# schematic.net
KiCad netlist of a schematic drawn in EasyEDA
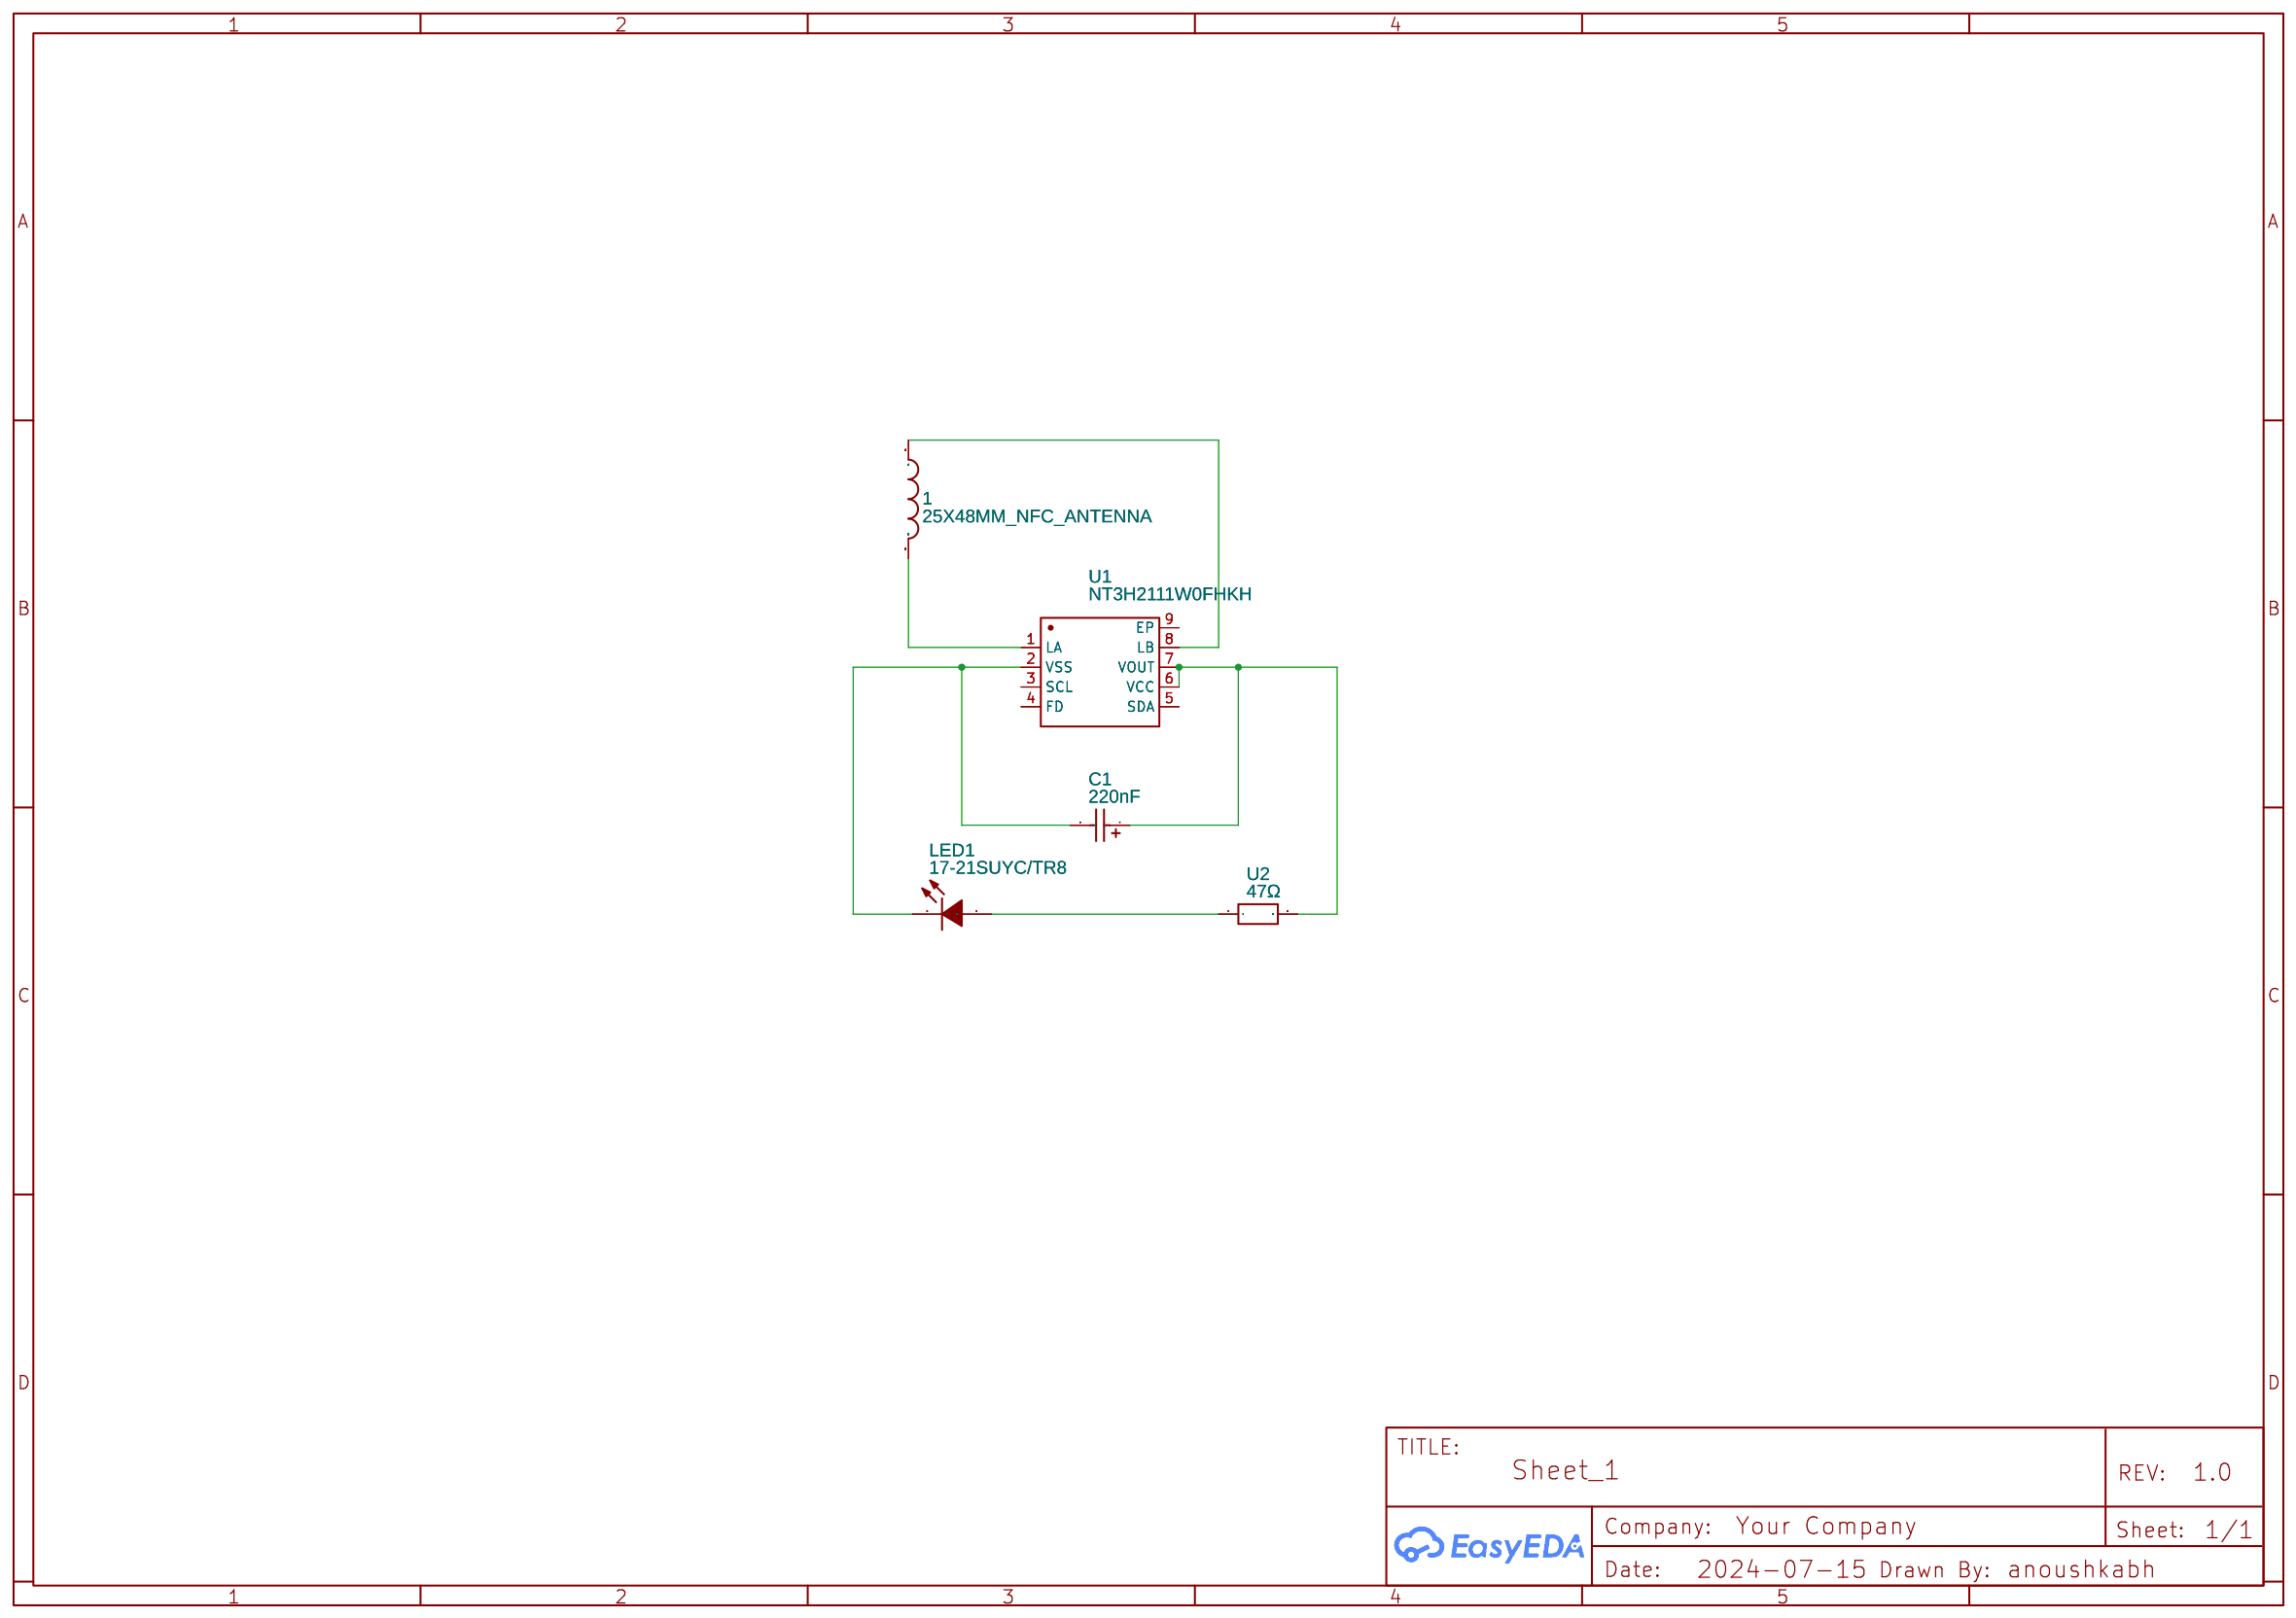
[diagram p0: schematic sheet]

(export (version "E")
  (design (tool "Eeschema 10.0.6"))
  (components
    (comp (ref "1") (value "25X48MM_NFC_ANTENNA") (libsource (lib "") (part "25X48MM_NFC_ANTENNA")))
    (comp (ref "C1")
      (value "220nF")
      (fields (field (name "Manufacturer Part") "TAJA224K035RNJ") (field (name "Manufacturer") "Kyocera AVX"))
      (libsource (lib "") (part "TAJA224K035RNJ"))
    )
    (comp (ref "LED1")
      (value "17-21SUYC/TR8")
      (fields (field (name "Manufacturer Part") "KT-0805黄灯") (field (name "Manufacturer") "KENTO"))
      (libsource (lib "") (part "17-21SUYC/TR8"))
    )
    (comp (ref "U1")
      (value "NT3H2111W0FHKH")
      (fields (field (name "Manufacturer") "NXP(恩智浦)"))
      (libsource (lib "") (part "NT3H2111W0FHKH"))
    )
    (comp (ref "U2")
      (value "47Ω")
      (fields (field (name "Manufacturer Part") "KNP1WS-47Ω±5%-XT52") (field (name "Manufacturer") "VO(翔胜)"))
      (libsource (lib "") (part "KNP1WS-47Ω±5%-XT52"))
    )
  )
  (nets
    (net (code "1") (name "Net-(LED1-+)") (class "Default")
      (node (ref "LED1") (pin "1") (pinfunction "+_1") (pintype "unspecified"))
      (node (ref "U2") (pin "1") (pinfunction "1_1") (pintype "unspecified"))
    )
    (net (code "2") (name "Net-(LED1--)") (class "Default")
      (node (ref "C1") (pin "2") (pinfunction "2_2") (pintype "input"))
      (node (ref "LED1") (pin "2") (pinfunction "-_2") (pintype "unspecified"))
      (node (ref "U1") (pin "2") (pinfunction "VSS_2") (pintype "unspecified"))
    )
    (net (code "3") (name "Net-(U1-LA)") (class "Default")
      (node (ref "1") (pin "P$2") (pinfunction "P$2_P$2") (pintype "bidirectional"))
      (node (ref "U1") (pin "1") (pinfunction "LA_1") (pintype "unspecified"))
    )
    (net (code "4") (name "Net-(U1-LB)") (class "Default")
      (node (ref "1") (pin "P$1") (pinfunction "P$1_P$1") (pintype "bidirectional"))
      (node (ref "U1") (pin "8") (pinfunction "LB_8") (pintype "unspecified"))
    )
    (net (code "5") (name "Net-(U1-VCC)") (class "Default")
      (node (ref "C1") (pin "1") (pinfunction "1_1") (pintype "input"))
      (node (ref "U1") (pin "6") (pinfunction "VCC_6") (pintype "unspecified"))
      (node (ref "U1") (pin "7") (pinfunction "VOUT_7") (pintype "unspecified"))
      (node (ref "U2") (pin "2") (pinfunction "2_2") (pintype "unspecified"))
    )
    (net (code "6") (name "unconnected-(U1-EP-Pad9)") (class "Default")
      (node (ref "U1") (pin "9") (pinfunction "EP_9") (pintype "unspecified"))
    )
    (net (code "7") (name "unconnected-(U1-FD-Pad4)") (class "Default")
      (node (ref "U1") (pin "4") (pinfunction "FD_4") (pintype "unspecified"))
    )
    (net (code "8") (name "unconnected-(U1-SCL-Pad3)") (class "Default")
      (node (ref "U1") (pin "3") (pinfunction "SCL_3") (pintype "unspecified"))
    )
    (net (code "9") (name "unconnected-(U1-SDA-Pad5)") (class "Default")
      (node (ref "U1") (pin "5") (pinfunction "SDA_5") (pintype "unspecified"))
    )
  )
)
